# tappytap.net
KiCad netlist of a schematic drawn in EAGLE
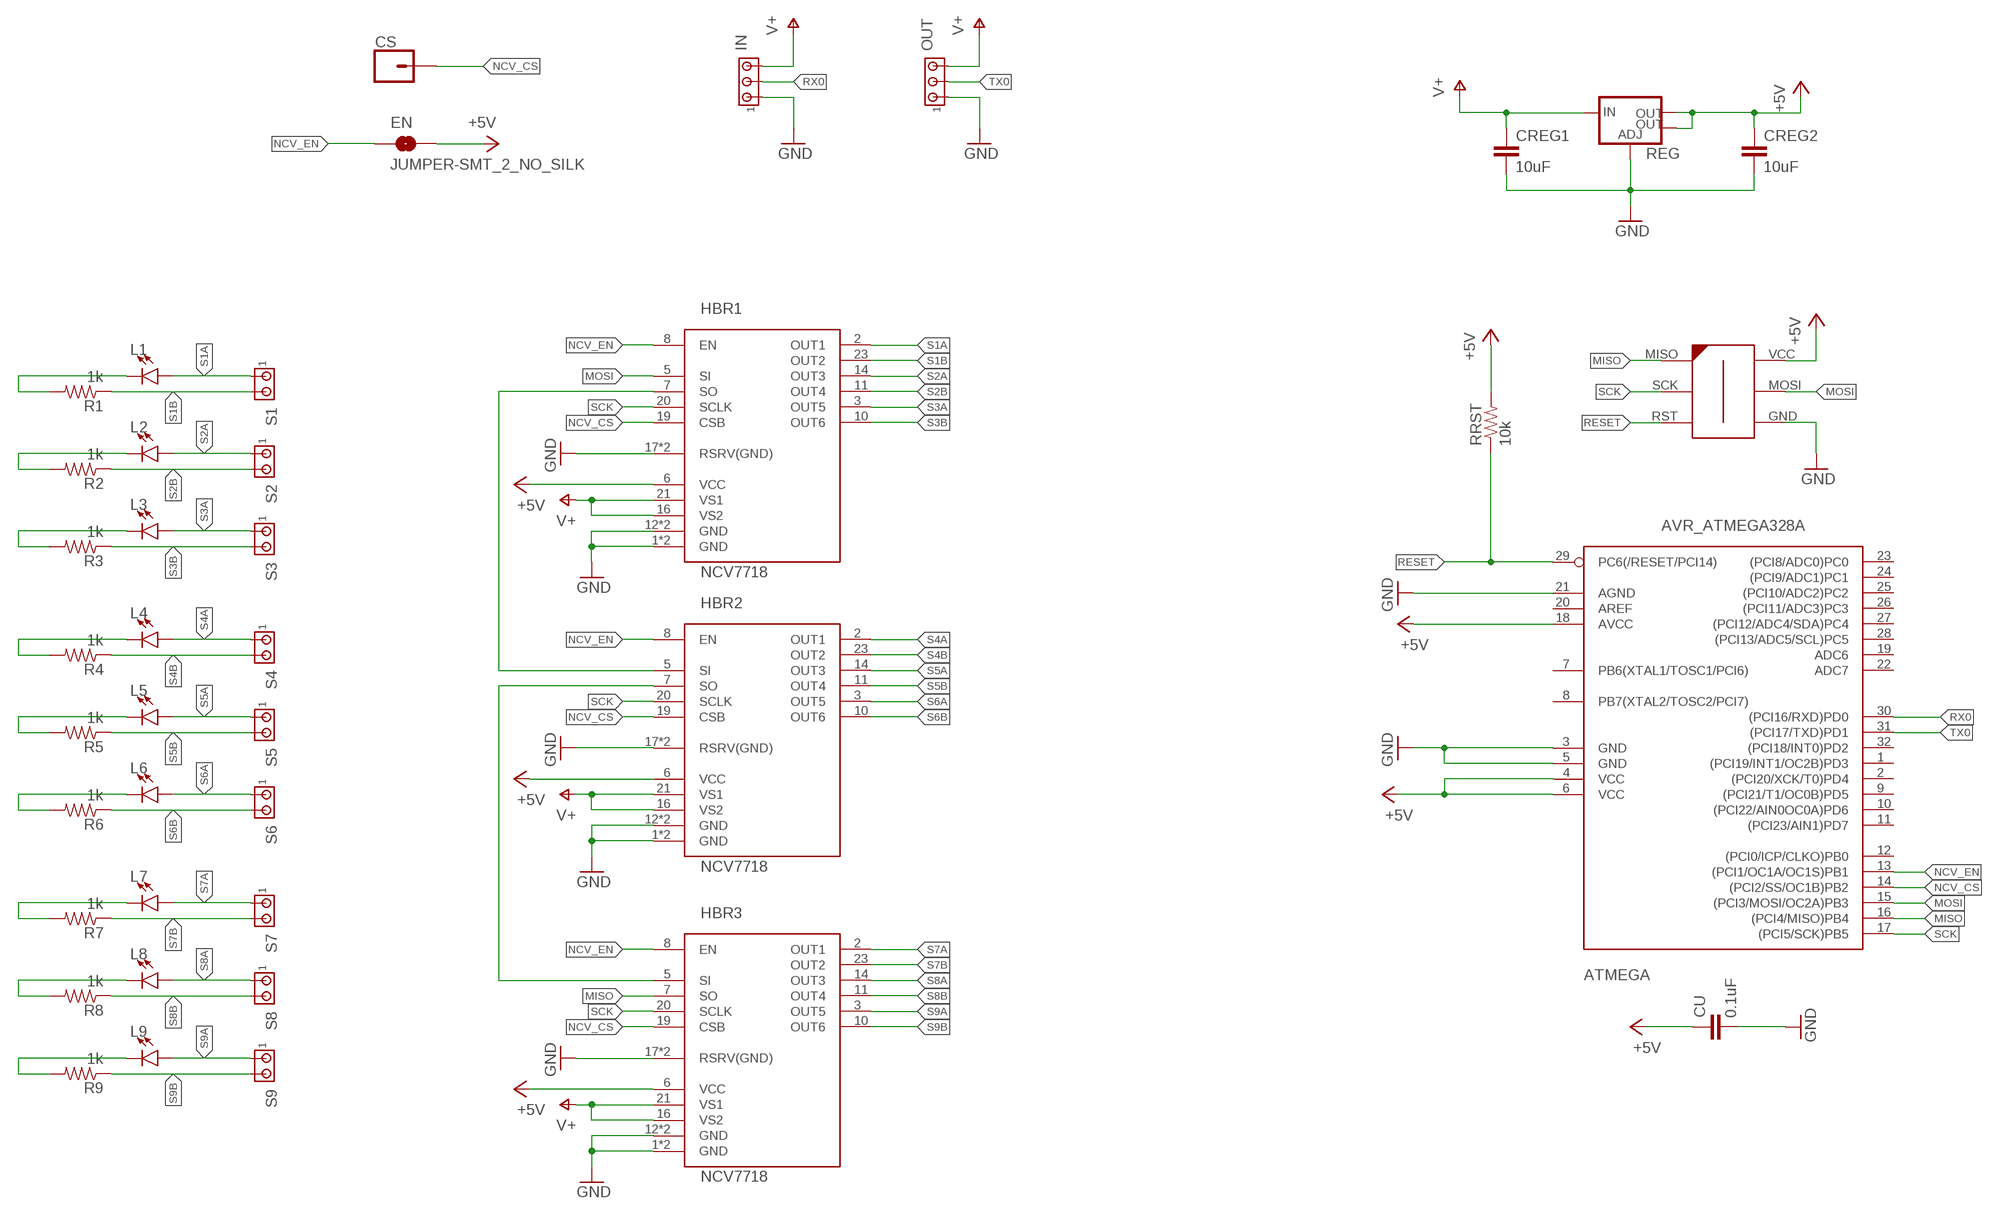
[diagram p0: schematic, sheet 1]

(export (version "E")
  (design (tool "Eeschema 10.0.6"))
  (components
    (comp (ref "ATMEGA")
      (value "AVR_ATMEGA328A")
      (footprint "eagle-import:AVR_TQFP32-08")
      (libsource (lib "eagle-import") (part "AVR_ATMEGA328A"))
    )
    (comp (ref "CREG1")
      (value "10uF")
      (footprint "eagle-import:C0603")
      (libsource (lib "eagle-import") (part "C-EUC0603"))
    )
    (comp (ref "CREG2")
      (value "10uF")
      (footprint "eagle-import:C0603")
      (libsource (lib "eagle-import") (part "C-EUC0603"))
    )
    (comp (ref "CS")
      (value "CONN_01")
      (footprint "eagle-import:1X01")
      (libsource (lib "eagle-import") (part "CONN_01"))
    )
    (comp (ref "CU")
      (value "0.1uF")
      (footprint "eagle-import:C0603")
      (libsource (lib "eagle-import") (part "C-EUC0603"))
    )
    (comp (ref "EN")
      (value "JUMPER-SMT_2_NO_SILK")
      (footprint "eagle-import:SMT-JUMPER_2_NO_SILK")
      (libsource (lib "eagle-import") (part "JUMPER-SMT_2_NO_SILK"))
    )
    (comp (ref "HBR1")
      (value "NCV7718")
      (footprint "eagle-import:24-SSOP")
      (libsource (lib "eagle-import") (part "NCV7718"))
    )
    (comp (ref "HBR2")
      (value "NCV7718")
      (footprint "eagle-import:24-SSOP")
      (libsource (lib "eagle-import") (part "NCV7718"))
    )
    (comp (ref "HBR3")
      (value "NCV7718")
      (footprint "eagle-import:24-SSOP")
      (libsource (lib "eagle-import") (part "NCV7718"))
    )
    (comp (ref "IN")
      (value "MTA03-100")
      (footprint "eagle-import:10X03MTA")
      (libsource (lib "eagle-import") (part "MTA03-100"))
    )
    (comp (ref "ISP")
      (value "AVR-ISP-6-EDGE")
      (footprint "eagle-import:6PAD_ISP")
      (libsource (lib "eagle-import") (part "AVR-ISP-6-EDGE"))
    )
    (comp (ref "L1")
      (value "LED0603")
      (footprint "eagle-import:LED-0603")
      (libsource (lib "eagle-import") (part "LED0603"))
    )
    (comp (ref "L2")
      (value "LED0603")
      (footprint "eagle-import:LED-0603")
      (libsource (lib "eagle-import") (part "LED0603"))
    )
    (comp (ref "L3")
      (value "LED0603")
      (footprint "eagle-import:LED-0603")
      (libsource (lib "eagle-import") (part "LED0603"))
    )
    (comp (ref "L4")
      (value "LED0603")
      (footprint "eagle-import:LED-0603")
      (libsource (lib "eagle-import") (part "LED0603"))
    )
    (comp (ref "L5")
      (value "LED0603")
      (footprint "eagle-import:LED-0603")
      (libsource (lib "eagle-import") (part "LED0603"))
    )
    (comp (ref "L6")
      (value "LED0603")
      (footprint "eagle-import:LED-0603")
      (libsource (lib "eagle-import") (part "LED0603"))
    )
    (comp (ref "L7")
      (value "LED0603")
      (footprint "eagle-import:LED-0603")
      (libsource (lib "eagle-import") (part "LED0603"))
    )
    (comp (ref "L8")
      (value "LED0603")
      (footprint "eagle-import:LED-0603")
      (libsource (lib "eagle-import") (part "LED0603"))
    )
    (comp (ref "L9")
      (value "LED0603")
      (footprint "eagle-import:LED-0603")
      (libsource (lib "eagle-import") (part "LED0603"))
    )
    (comp (ref "OUT")
      (value "MTA03-100")
      (footprint "eagle-import:10X03MTA")
      (libsource (lib "eagle-import") (part "MTA03-100"))
    )
    (comp (ref "R1")
      (value "1k")
      (footprint "eagle-import:R0603")
      (libsource (lib "eagle-import") (part "R-US_R0603"))
    )
    (comp (ref "R2")
      (value "1k")
      (footprint "eagle-import:R0603")
      (libsource (lib "eagle-import") (part "R-US_R0603"))
    )
    (comp (ref "R3")
      (value "1k")
      (footprint "eagle-import:R0603")
      (libsource (lib "eagle-import") (part "R-US_R0603"))
    )
    (comp (ref "R4")
      (value "1k")
      (footprint "eagle-import:R0603")
      (libsource (lib "eagle-import") (part "R-US_R0603"))
    )
    (comp (ref "R5")
      (value "1k")
      (footprint "eagle-import:R0603")
      (libsource (lib "eagle-import") (part "R-US_R0603"))
    )
    (comp (ref "R6")
      (value "1k")
      (footprint "eagle-import:R0603")
      (libsource (lib "eagle-import") (part "R-US_R0603"))
    )
    (comp (ref "R7")
      (value "1k")
      (footprint "eagle-import:R0603")
      (libsource (lib "eagle-import") (part "R-US_R0603"))
    )
    (comp (ref "R8")
      (value "1k")
      (footprint "eagle-import:R0603")
      (libsource (lib "eagle-import") (part "R-US_R0603"))
    )
    (comp (ref "R9")
      (value "1k")
      (footprint "eagle-import:R0603")
      (libsource (lib "eagle-import") (part "R-US_R0603"))
    )
    (comp (ref "REG")
      (value "V_REG_LM1117SOT223")
      (footprint "eagle-import:SOT223")
      (libsource (lib "eagle-import") (part "V_REG_LM1117SOT223"))
    )
    (comp (ref "RRST")
      (value "10k")
      (footprint "eagle-import:R0603")
      (libsource (lib "eagle-import") (part "R-US_R0603"))
    )
    (comp (ref "S1")
      (value "MTA02-100")
      (footprint "eagle-import:10X02MTA")
      (libsource (lib "eagle-import") (part "MTA02-100"))
    )
    (comp (ref "S2")
      (value "MTA02-100")
      (footprint "eagle-import:10X02MTA")
      (libsource (lib "eagle-import") (part "MTA02-100"))
    )
    (comp (ref "S3")
      (value "MTA02-100")
      (footprint "eagle-import:10X02MTA")
      (libsource (lib "eagle-import") (part "MTA02-100"))
    )
    (comp (ref "S4")
      (value "MTA02-100")
      (footprint "eagle-import:10X02MTA")
      (libsource (lib "eagle-import") (part "MTA02-100"))
    )
    (comp (ref "S5")
      (value "MTA02-100")
      (footprint "eagle-import:10X02MTA")
      (libsource (lib "eagle-import") (part "MTA02-100"))
    )
    (comp (ref "S6")
      (value "MTA02-100")
      (footprint "eagle-import:10X02MTA")
      (libsource (lib "eagle-import") (part "MTA02-100"))
    )
    (comp (ref "S7")
      (value "MTA02-100")
      (footprint "eagle-import:10X02MTA")
      (libsource (lib "eagle-import") (part "MTA02-100"))
    )
    (comp (ref "S8")
      (value "MTA02-100")
      (footprint "eagle-import:10X02MTA")
      (libsource (lib "eagle-import") (part "MTA02-100"))
    )
    (comp (ref "S9")
      (value "MTA02-100")
      (footprint "eagle-import:10X02MTA")
      (libsource (lib "eagle-import") (part "MTA02-100"))
    )
  )
  (nets
    (net (code "1") (name "+5V") (class "Default")
      (node (ref "ATMEGA") (pin "18") (pinfunction "AVCC_18") (pintype "bidirectional"))
      (node (ref "ATMEGA") (pin "4") (pinfunction "VCC_4") (pintype "power_in"))
      (node (ref "ATMEGA") (pin "6") (pinfunction "VCC_6") (pintype "power_in"))
      (node (ref "CREG2") (pin "1") (pinfunction "1_1") (pintype "passive"))
      (node (ref "CU") (pin "1") (pinfunction "1_1") (pintype "passive"))
      (node (ref "EN") (pin "2") (pinfunction "2_2") (pintype "passive"))
      (node (ref "HBR1") (pin "6") (pinfunction "VCC_6") (pintype "bidirectional"))
      (node (ref "HBR2") (pin "6") (pinfunction "VCC_6") (pintype "bidirectional"))
      (node (ref "HBR3") (pin "6") (pinfunction "VCC_6") (pintype "bidirectional"))
      (node (ref "ISP") (pin "VCC") (pinfunction "P$6_VCC") (pintype "bidirectional"))
      (node (ref "REG") (pin "2") (pinfunction "OUT_2") (pintype "output"))
      (node (ref "REG") (pin "4") (pinfunction "OUT_4") (pintype "output"))
      (node (ref "RRST") (pin "2") (pinfunction "2_2") (pintype "passive"))
    )
    (net (code "2") (name "GND") (class "Default")
      (node (ref "ATMEGA") (pin "21") (pinfunction "AGND_21") (pintype "bidirectional"))
      (node (ref "ATMEGA") (pin "3") (pinfunction "GND_3") (pintype "power_in"))
      (node (ref "ATMEGA") (pin "5") (pinfunction "GND_5") (pintype "power_in"))
      (node (ref "CREG1") (pin "2") (pinfunction "2_2") (pintype "passive"))
      (node (ref "CREG2") (pin "2") (pinfunction "2_2") (pintype "passive"))
      (node (ref "CU") (pin "2") (pinfunction "2_2") (pintype "passive"))
      (node (ref "HBR1") (pin "1") (pinfunction "GND_1") (pintype "bidirectional"))
      (node (ref "HBR1") (pin "12") (pinfunction "GND_12") (pintype "bidirectional"))
      (node (ref "HBR1") (pin "13") (pinfunction "GND_13") (pintype "bidirectional"))
      (node (ref "HBR1") (pin "17") (pinfunction "RSRV(GND)_17") (pintype "bidirectional"))
      (node (ref "HBR1") (pin "18") (pinfunction "RSRV(GND)_18") (pintype "bidirectional"))
      (node (ref "HBR1") (pin "24") (pinfunction "GND_24") (pintype "bidirectional"))
      (node (ref "HBR2") (pin "1") (pinfunction "GND_1") (pintype "bidirectional"))
      (node (ref "HBR2") (pin "12") (pinfunction "GND_12") (pintype "bidirectional"))
      (node (ref "HBR2") (pin "13") (pinfunction "GND_13") (pintype "bidirectional"))
      (node (ref "HBR2") (pin "17") (pinfunction "RSRV(GND)_17") (pintype "bidirectional"))
      (node (ref "HBR2") (pin "18") (pinfunction "RSRV(GND)_18") (pintype "bidirectional"))
      (node (ref "HBR2") (pin "24") (pinfunction "GND_24") (pintype "bidirectional"))
      (node (ref "HBR3") (pin "1") (pinfunction "GND_1") (pintype "bidirectional"))
      (node (ref "HBR3") (pin "12") (pinfunction "GND_12") (pintype "bidirectional"))
      (node (ref "HBR3") (pin "13") (pinfunction "GND_13") (pintype "bidirectional"))
      (node (ref "HBR3") (pin "17") (pinfunction "RSRV(GND)_17") (pintype "bidirectional"))
      (node (ref "HBR3") (pin "18") (pinfunction "RSRV(GND)_18") (pintype "bidirectional"))
      (node (ref "HBR3") (pin "24") (pinfunction "GND_24") (pintype "bidirectional"))
      (node (ref "IN") (pin "1") (pinfunction "1_1") (pintype "passive"))
      (node (ref "ISP") (pin "GND") (pinfunction "P$4_GND") (pintype "bidirectional"))
      (node (ref "OUT") (pin "1") (pinfunction "1_1") (pintype "passive"))
      (node (ref "REG") (pin "1") (pinfunction "ADJ_1") (pintype "input"))
    )
    (net (code "3") (name "MISO") (class "Default")
      (node (ref "ATMEGA") (pin "16") (pinfunction "(PCI4/MISO)PB4_16") (pintype "bidirectional"))
      (node (ref "HBR3") (pin "7") (pinfunction "SO_7") (pintype "bidirectional"))
      (node (ref "ISP") (pin "MISO") (pinfunction "P$1_MISO") (pintype "bidirectional"))
    )
    (net (code "4") (name "MOSI") (class "Default")
      (node (ref "ATMEGA") (pin "15") (pinfunction "(PCI3/MOSI/OC2A)PB3_15") (pintype "bidirectional"))
      (node (ref "HBR1") (pin "5") (pinfunction "SI_5") (pintype "bidirectional"))
      (node (ref "ISP") (pin "MOSI") (pinfunction "P$5_MOSI") (pintype "bidirectional"))
    )
    (net (code "5") (name "NCV_CS") (class "Default")
      (node (ref "ATMEGA") (pin "14") (pinfunction "(PCI2/SS/OC1B)PB2_14") (pintype "bidirectional"))
      (node (ref "CS") (pin "1") (pinfunction "1_1") (pintype "passive"))
      (node (ref "HBR1") (pin "19") (pinfunction "CSB_19") (pintype "bidirectional"))
      (node (ref "HBR2") (pin "19") (pinfunction "CSB_19") (pintype "bidirectional"))
      (node (ref "HBR3") (pin "19") (pinfunction "CSB_19") (pintype "bidirectional"))
    )
    (net (code "6") (name "NCV_EN") (class "Default")
      (node (ref "ATMEGA") (pin "13") (pinfunction "(PCI1/OC1A/OC1S)PB1_13") (pintype "bidirectional"))
      (node (ref "EN") (pin "1") (pinfunction "1_1") (pintype "passive"))
      (node (ref "HBR1") (pin "8") (pinfunction "EN_8") (pintype "bidirectional"))
      (node (ref "HBR2") (pin "8") (pinfunction "EN_8") (pintype "bidirectional"))
      (node (ref "HBR3") (pin "8") (pinfunction "EN_8") (pintype "bidirectional"))
    )
    (net (code "7") (name "Net-(HBR1-SO)") (class "Default")
      (node (ref "HBR1") (pin "7") (pinfunction "SO_7") (pintype "bidirectional"))
      (node (ref "HBR2") (pin "5") (pinfunction "SI_5") (pintype "bidirectional"))
    )
    (net (code "8") (name "Net-(HBR2-SO)") (class "Default")
      (node (ref "HBR2") (pin "7") (pinfunction "SO_7") (pintype "bidirectional"))
      (node (ref "HBR3") (pin "5") (pinfunction "SI_5") (pintype "bidirectional"))
    )
    (net (code "9") (name "Net-(L1-PadC)") (class "Default")
      (node (ref "L1") (pin "C") (pinfunction "C_C") (pintype "passive"))
      (node (ref "R1") (pin "2") (pinfunction "2_2") (pintype "passive"))
    )
    (net (code "10") (name "Net-(L2-PadC)") (class "Default")
      (node (ref "L2") (pin "C") (pinfunction "C_C") (pintype "passive"))
      (node (ref "R2") (pin "2") (pinfunction "2_2") (pintype "passive"))
    )
    (net (code "11") (name "Net-(L3-PadC)") (class "Default")
      (node (ref "L3") (pin "C") (pinfunction "C_C") (pintype "passive"))
      (node (ref "R3") (pin "2") (pinfunction "2_2") (pintype "passive"))
    )
    (net (code "12") (name "Net-(L4-PadC)") (class "Default")
      (node (ref "L4") (pin "C") (pinfunction "C_C") (pintype "passive"))
      (node (ref "R4") (pin "2") (pinfunction "2_2") (pintype "passive"))
    )
    (net (code "13") (name "Net-(L5-PadC)") (class "Default")
      (node (ref "L5") (pin "C") (pinfunction "C_C") (pintype "passive"))
      (node (ref "R5") (pin "2") (pinfunction "2_2") (pintype "passive"))
    )
    (net (code "14") (name "Net-(L6-PadC)") (class "Default")
      (node (ref "L6") (pin "C") (pinfunction "C_C") (pintype "passive"))
      (node (ref "R6") (pin "2") (pinfunction "2_2") (pintype "passive"))
    )
    (net (code "15") (name "Net-(L7-PadC)") (class "Default")
      (node (ref "L7") (pin "C") (pinfunction "C_C") (pintype "passive"))
      (node (ref "R7") (pin "2") (pinfunction "2_2") (pintype "passive"))
    )
    (net (code "16") (name "Net-(L8-PadC)") (class "Default")
      (node (ref "L8") (pin "C") (pinfunction "C_C") (pintype "passive"))
      (node (ref "R8") (pin "2") (pinfunction "2_2") (pintype "passive"))
    )
    (net (code "17") (name "Net-(L9-PadC)") (class "Default")
      (node (ref "L9") (pin "C") (pinfunction "C_C") (pintype "passive"))
      (node (ref "R9") (pin "2") (pinfunction "2_2") (pintype "passive"))
    )
    (net (code "18") (name "RESET") (class "Default")
      (node (ref "ATMEGA") (pin "29") (pinfunction "PC6(/RESET/PCI14)_29") (pintype "bidirectional"))
      (node (ref "ISP") (pin "RST") (pinfunction "P$3_RST") (pintype "bidirectional"))
      (node (ref "RRST") (pin "1") (pinfunction "1_1") (pintype "passive"))
    )
    (net (code "19") (name "RX0") (class "Default")
      (node (ref "ATMEGA") (pin "30") (pinfunction "(PCI16/RXD)PD0_30") (pintype "bidirectional"))
      (node (ref "IN") (pin "2") (pinfunction "2_2") (pintype "passive"))
    )
    (net (code "20") (name "S1A") (class "Default")
      (node (ref "HBR1") (pin "2") (pinfunction "OUT1_2") (pintype "bidirectional"))
      (node (ref "L1") (pin "A") (pinfunction "A_A") (pintype "passive"))
      (node (ref "S1") (pin "1") (pinfunction "1_1") (pintype "passive"))
    )
    (net (code "21") (name "S1B") (class "Default")
      (node (ref "HBR1") (pin "23") (pinfunction "OUT2_23") (pintype "bidirectional"))
      (node (ref "R1") (pin "1") (pinfunction "1_1") (pintype "passive"))
      (node (ref "S1") (pin "2") (pinfunction "2_2") (pintype "passive"))
    )
    (net (code "22") (name "S2A") (class "Default")
      (node (ref "HBR1") (pin "14") (pinfunction "OUT3_14") (pintype "bidirectional"))
      (node (ref "L2") (pin "A") (pinfunction "A_A") (pintype "passive"))
      (node (ref "S2") (pin "1") (pinfunction "1_1") (pintype "passive"))
    )
    (net (code "23") (name "S2B") (class "Default")
      (node (ref "HBR1") (pin "11") (pinfunction "OUT4_11") (pintype "bidirectional"))
      (node (ref "R2") (pin "1") (pinfunction "1_1") (pintype "passive"))
      (node (ref "S2") (pin "2") (pinfunction "2_2") (pintype "passive"))
    )
    (net (code "24") (name "S3A") (class "Default")
      (node (ref "HBR1") (pin "3") (pinfunction "OUT5_3") (pintype "bidirectional"))
      (node (ref "L3") (pin "A") (pinfunction "A_A") (pintype "passive"))
      (node (ref "S3") (pin "1") (pinfunction "1_1") (pintype "passive"))
    )
    (net (code "25") (name "S3B") (class "Default")
      (node (ref "HBR1") (pin "10") (pinfunction "OUT6_10") (pintype "bidirectional"))
      (node (ref "R3") (pin "1") (pinfunction "1_1") (pintype "passive"))
      (node (ref "S3") (pin "2") (pinfunction "2_2") (pintype "passive"))
    )
    (net (code "26") (name "S4A") (class "Default")
      (node (ref "HBR2") (pin "2") (pinfunction "OUT1_2") (pintype "bidirectional"))
      (node (ref "L4") (pin "A") (pinfunction "A_A") (pintype "passive"))
      (node (ref "S4") (pin "1") (pinfunction "1_1") (pintype "passive"))
    )
    (net (code "27") (name "S4B") (class "Default")
      (node (ref "HBR2") (pin "23") (pinfunction "OUT2_23") (pintype "bidirectional"))
      (node (ref "R4") (pin "1") (pinfunction "1_1") (pintype "passive"))
      (node (ref "S4") (pin "2") (pinfunction "2_2") (pintype "passive"))
    )
    (net (code "28") (name "S5A") (class "Default")
      (node (ref "HBR2") (pin "14") (pinfunction "OUT3_14") (pintype "bidirectional"))
      (node (ref "L5") (pin "A") (pinfunction "A_A") (pintype "passive"))
      (node (ref "S5") (pin "1") (pinfunction "1_1") (pintype "passive"))
    )
    (net (code "29") (name "S5B") (class "Default")
      (node (ref "HBR2") (pin "11") (pinfunction "OUT4_11") (pintype "bidirectional"))
      (node (ref "R5") (pin "1") (pinfunction "1_1") (pintype "passive"))
      (node (ref "S5") (pin "2") (pinfunction "2_2") (pintype "passive"))
    )
    (net (code "30") (name "S6A") (class "Default")
      (node (ref "HBR2") (pin "3") (pinfunction "OUT5_3") (pintype "bidirectional"))
      (node (ref "L6") (pin "A") (pinfunction "A_A") (pintype "passive"))
      (node (ref "S6") (pin "1") (pinfunction "1_1") (pintype "passive"))
    )
    (net (code "31") (name "S6B") (class "Default")
      (node (ref "HBR2") (pin "10") (pinfunction "OUT6_10") (pintype "bidirectional"))
      (node (ref "R6") (pin "1") (pinfunction "1_1") (pintype "passive"))
      (node (ref "S6") (pin "2") (pinfunction "2_2") (pintype "passive"))
    )
    (net (code "32") (name "S7A") (class "Default")
      (node (ref "HBR3") (pin "2") (pinfunction "OUT1_2") (pintype "bidirectional"))
      (node (ref "L7") (pin "A") (pinfunction "A_A") (pintype "passive"))
      (node (ref "S7") (pin "1") (pinfunction "1_1") (pintype "passive"))
    )
    (net (code "33") (name "S7B") (class "Default")
      (node (ref "HBR3") (pin "23") (pinfunction "OUT2_23") (pintype "bidirectional"))
      (node (ref "R7") (pin "1") (pinfunction "1_1") (pintype "passive"))
      (node (ref "S7") (pin "2") (pinfunction "2_2") (pintype "passive"))
    )
    (net (code "34") (name "S8A") (class "Default")
      (node (ref "HBR3") (pin "14") (pinfunction "OUT3_14") (pintype "bidirectional"))
      (node (ref "L8") (pin "A") (pinfunction "A_A") (pintype "passive"))
      (node (ref "S8") (pin "1") (pinfunction "1_1") (pintype "passive"))
    )
    (net (code "35") (name "S8B") (class "Default")
      (node (ref "HBR3") (pin "11") (pinfunction "OUT4_11") (pintype "bidirectional"))
      (node (ref "R8") (pin "1") (pinfunction "1_1") (pintype "passive"))
      (node (ref "S8") (pin "2") (pinfunction "2_2") (pintype "passive"))
    )
    (net (code "36") (name "S9A") (class "Default")
      (node (ref "HBR3") (pin "3") (pinfunction "OUT5_3") (pintype "bidirectional"))
      (node (ref "L9") (pin "A") (pinfunction "A_A") (pintype "passive"))
      (node (ref "S9") (pin "1") (pinfunction "1_1") (pintype "passive"))
    )
    (net (code "37") (name "S9B") (class "Default")
      (node (ref "HBR3") (pin "10") (pinfunction "OUT6_10") (pintype "bidirectional"))
      (node (ref "R9") (pin "1") (pinfunction "1_1") (pintype "passive"))
      (node (ref "S9") (pin "2") (pinfunction "2_2") (pintype "passive"))
    )
    (net (code "38") (name "SCK") (class "Default")
      (node (ref "ATMEGA") (pin "17") (pinfunction "(PCI5/SCK)PB5_17") (pintype "bidirectional"))
      (node (ref "HBR1") (pin "20") (pinfunction "SCLK_20") (pintype "bidirectional"))
      (node (ref "HBR2") (pin "20") (pinfunction "SCLK_20") (pintype "bidirectional"))
      (node (ref "HBR3") (pin "20") (pinfunction "SCLK_20") (pintype "bidirectional"))
      (node (ref "ISP") (pin "SCK") (pinfunction "P$2_SCK") (pintype "bidirectional"))
    )
    (net (code "39") (name "TX0") (class "Default")
      (node (ref "ATMEGA") (pin "31") (pinfunction "(PCI17/TXD)PD1_31") (pintype "bidirectional"))
      (node (ref "OUT") (pin "2") (pinfunction "2_2") (pintype "passive"))
    )
    (net (code "40") (name "V+") (class "Default")
      (node (ref "CREG1") (pin "1") (pinfunction "1_1") (pintype "passive"))
      (node (ref "HBR1") (pin "16") (pinfunction "VS2_16") (pintype "bidirectional"))
      (node (ref "HBR1") (pin "21") (pinfunction "VS1_21") (pintype "bidirectional"))
      (node (ref "HBR2") (pin "16") (pinfunction "VS2_16") (pintype "bidirectional"))
      (node (ref "HBR2") (pin "21") (pinfunction "VS1_21") (pintype "bidirectional"))
      (node (ref "HBR3") (pin "16") (pinfunction "VS2_16") (pintype "bidirectional"))
      (node (ref "HBR3") (pin "21") (pinfunction "VS1_21") (pintype "bidirectional"))
      (node (ref "IN") (pin "3") (pinfunction "3_3") (pintype "passive"))
      (node (ref "OUT") (pin "3") (pinfunction "3_3") (pintype "passive"))
      (node (ref "REG") (pin "3") (pinfunction "IN_3") (pintype "input"))
    )
    (net (code "41") (name "unconnected-(ATMEGA-(PCI0{slash}ICP{slash}CLKO)PB0-Pad12)") (class "Default")
      (node (ref "ATMEGA") (pin "12") (pinfunction "(PCI0/ICP/CLKO)PB0_12") (pintype "bidirectional"))
    )
    (net (code "42") (name "unconnected-(ATMEGA-(PCI8{slash}ADC0)PC0-Pad23)") (class "Default")
      (node (ref "ATMEGA") (pin "23") (pinfunction "(PCI8/ADC0)PC0_23") (pintype "bidirectional"))
    )
    (net (code "43") (name "unconnected-(ATMEGA-(PCI9{slash}ADC1)PC1-Pad24)") (class "Default")
      (node (ref "ATMEGA") (pin "24") (pinfunction "(PCI9/ADC1)PC1_24") (pintype "bidirectional"))
    )
    (net (code "44") (name "unconnected-(ATMEGA-(PCI10{slash}ADC2)PC2-Pad25)") (class "Default")
      (node (ref "ATMEGA") (pin "25") (pinfunction "(PCI10/ADC2)PC2_25") (pintype "bidirectional"))
    )
    (net (code "45") (name "unconnected-(ATMEGA-(PCI11{slash}ADC3)PC3-Pad26)") (class "Default")
      (node (ref "ATMEGA") (pin "26") (pinfunction "(PCI11/ADC3)PC3_26") (pintype "bidirectional"))
    )
    (net (code "46") (name "unconnected-(ATMEGA-(PCI12{slash}ADC4{slash}SDA)PC4-Pad27)") (class "Default")
      (node (ref "ATMEGA") (pin "27") (pinfunction "(PCI12/ADC4/SDA)PC4_27") (pintype "bidirectional"))
    )
    (net (code "47") (name "unconnected-(ATMEGA-(PCI13{slash}ADC5{slash}SCL)PC5-Pad28)") (class "Default")
      (node (ref "ATMEGA") (pin "28") (pinfunction "(PCI13/ADC5/SCL)PC5_28") (pintype "bidirectional"))
    )
    (net (code "48") (name "unconnected-(ATMEGA-(PCI18{slash}INT0)PD2-Pad32)") (class "Default")
      (node (ref "ATMEGA") (pin "32") (pinfunction "(PCI18/INT0)PD2_32") (pintype "bidirectional"))
    )
    (net (code "49") (name "unconnected-(ATMEGA-(PCI19{slash}INT1{slash}OC2B)PD3-Pad1)") (class "Default")
      (node (ref "ATMEGA") (pin "1") (pinfunction "(PCI19/INT1/OC2B)PD3_1") (pintype "bidirectional"))
    )
    (net (code "50") (name "unconnected-(ATMEGA-(PCI20{slash}XCK{slash}T0)PD4-Pad2)") (class "Default")
      (node (ref "ATMEGA") (pin "2") (pinfunction "(PCI20/XCK/T0)PD4_2") (pintype "bidirectional"))
    )
    (net (code "51") (name "unconnected-(ATMEGA-(PCI21{slash}T1{slash}OC0B)PD5-Pad9)") (class "Default")
      (node (ref "ATMEGA") (pin "9") (pinfunction "(PCI21/T1/OC0B)PD5_9") (pintype "bidirectional"))
    )
    (net (code "52") (name "unconnected-(ATMEGA-(PCI22{slash}AIN0OC0A)PD6-Pad10)") (class "Default")
      (node (ref "ATMEGA") (pin "10") (pinfunction "(PCI22/AIN0OC0A)PD6_10") (pintype "bidirectional"))
    )
    (net (code "53") (name "unconnected-(ATMEGA-(PCI23{slash}AIN1)PD7-Pad11)") (class "Default")
      (node (ref "ATMEGA") (pin "11") (pinfunction "(PCI23/AIN1)PD7_11") (pintype "bidirectional"))
    )
    (net (code "54") (name "unconnected-(ATMEGA-ADC6-Pad19)") (class "Default")
      (node (ref "ATMEGA") (pin "19") (pinfunction "ADC6_19") (pintype "bidirectional"))
    )
    (net (code "55") (name "unconnected-(ATMEGA-ADC7-Pad22)") (class "Default")
      (node (ref "ATMEGA") (pin "22") (pinfunction "ADC7_22") (pintype "bidirectional"))
    )
    (net (code "56") (name "unconnected-(ATMEGA-AREF-Pad20)") (class "Default")
      (node (ref "ATMEGA") (pin "20") (pinfunction "AREF_20") (pintype "bidirectional"))
    )
    (net (code "57") (name "unconnected-(ATMEGA-PB6(XTAL1{slash}TOSC1{slash}PCI6)-Pad7)") (class "Default")
      (node (ref "ATMEGA") (pin "7") (pinfunction "PB6(XTAL1/TOSC1/PCI6)_7") (pintype "bidirectional"))
    )
    (net (code "58") (name "unconnected-(ATMEGA-PB7(XTAL2{slash}TOSC2{slash}PCI7)-Pad8)") (class "Default")
      (node (ref "ATMEGA") (pin "8") (pinfunction "PB7(XTAL2/TOSC2/PCI7)_8") (pintype "bidirectional"))
    )
  )
)
